# Galga.net
KiCad netlist of a schematic drawn in EAGLE
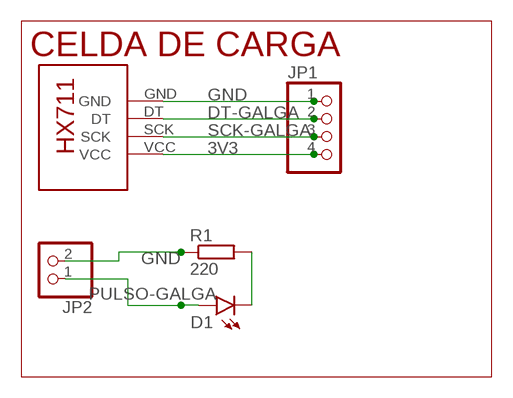
[diagram p0: schematic, sheet 1]

(export (version "E")
  (design (tool "Eeschema 10.0.6"))
  (components
    (comp (ref "D1")
      (value "LED3MM")
      (footprint "eagle-import:LED3MM")
      (libsource (lib "eagle-import") (part "LED3MM"))
    )
    (comp (ref "JP1")
      (value "PINHD-1X4")
      (footprint "eagle-import:1X04")
      (libsource (lib "eagle-import") (part "PINHD-1X4"))
    )
    (comp (ref "JP2")
      (value "PINHD-1X2")
      (footprint "eagle-import:1X02")
      (libsource (lib "eagle-import") (part "PINHD-1X2"))
    )
    (comp (ref "R1")
      (value "220")
      (footprint "eagle-import:0204_7")
      (libsource (lib "eagle-import") (part "R-EU_0204/7"))
    )
    (comp (ref "U$2")
      (value "HX-711")
      (footprint "eagle-import:HX-711")
      (libsource (lib "eagle-import") (part "HX-711"))
    )
  )
  (nets
    (net (code "1") (name "/3V3") (class "Default")
      (node (ref "JP1") (pin "4") (pinfunction "4_4") (pintype "passive"))
      (node (ref "U$2") (pin "VCC") (pinfunction "VCC_VCC") (pintype "bidirectional"))
    )
    (net (code "2") (name "/DT-GALGA") (class "Default")
      (node (ref "JP1") (pin "2") (pinfunction "2_2") (pintype "passive"))
      (node (ref "U$2") (pin "DT") (pinfunction "DT_DT") (pintype "bidirectional"))
    )
    (net (code "3") (name "/GND") (class "Default")
      (node (ref "JP1") (pin "1") (pinfunction "1_1") (pintype "passive"))
      (node (ref "JP2") (pin "2") (pinfunction "2_2") (pintype "passive"))
      (node (ref "R1") (pin "1") (pinfunction "1_1") (pintype "passive"))
      (node (ref "U$2") (pin "GND") (pinfunction "GND_GND") (pintype "bidirectional"))
    )
    (net (code "4") (name "/PULSO-GALGA") (class "Default")
      (node (ref "D1") (pin "A") (pinfunction "A_A") (pintype "passive"))
      (node (ref "JP2") (pin "1") (pinfunction "1_1") (pintype "passive"))
    )
    (net (code "5") (name "/SCK-GALGA") (class "Default")
      (node (ref "JP1") (pin "3") (pinfunction "3_3") (pintype "passive"))
      (node (ref "U$2") (pin "SCK") (pinfunction "SCK_SCK") (pintype "bidirectional"))
    )
    (net (code "6") (name "Net-(D1-C)") (class "Default")
      (node (ref "D1") (pin "K") (pinfunction "C_K") (pintype "passive"))
      (node (ref "R1") (pin "2") (pinfunction "2_2") (pintype "passive"))
    )
  )
)
